# OP_Current_Fun-V0.net
KiCad netlist of a schematic drawn in EAGLE
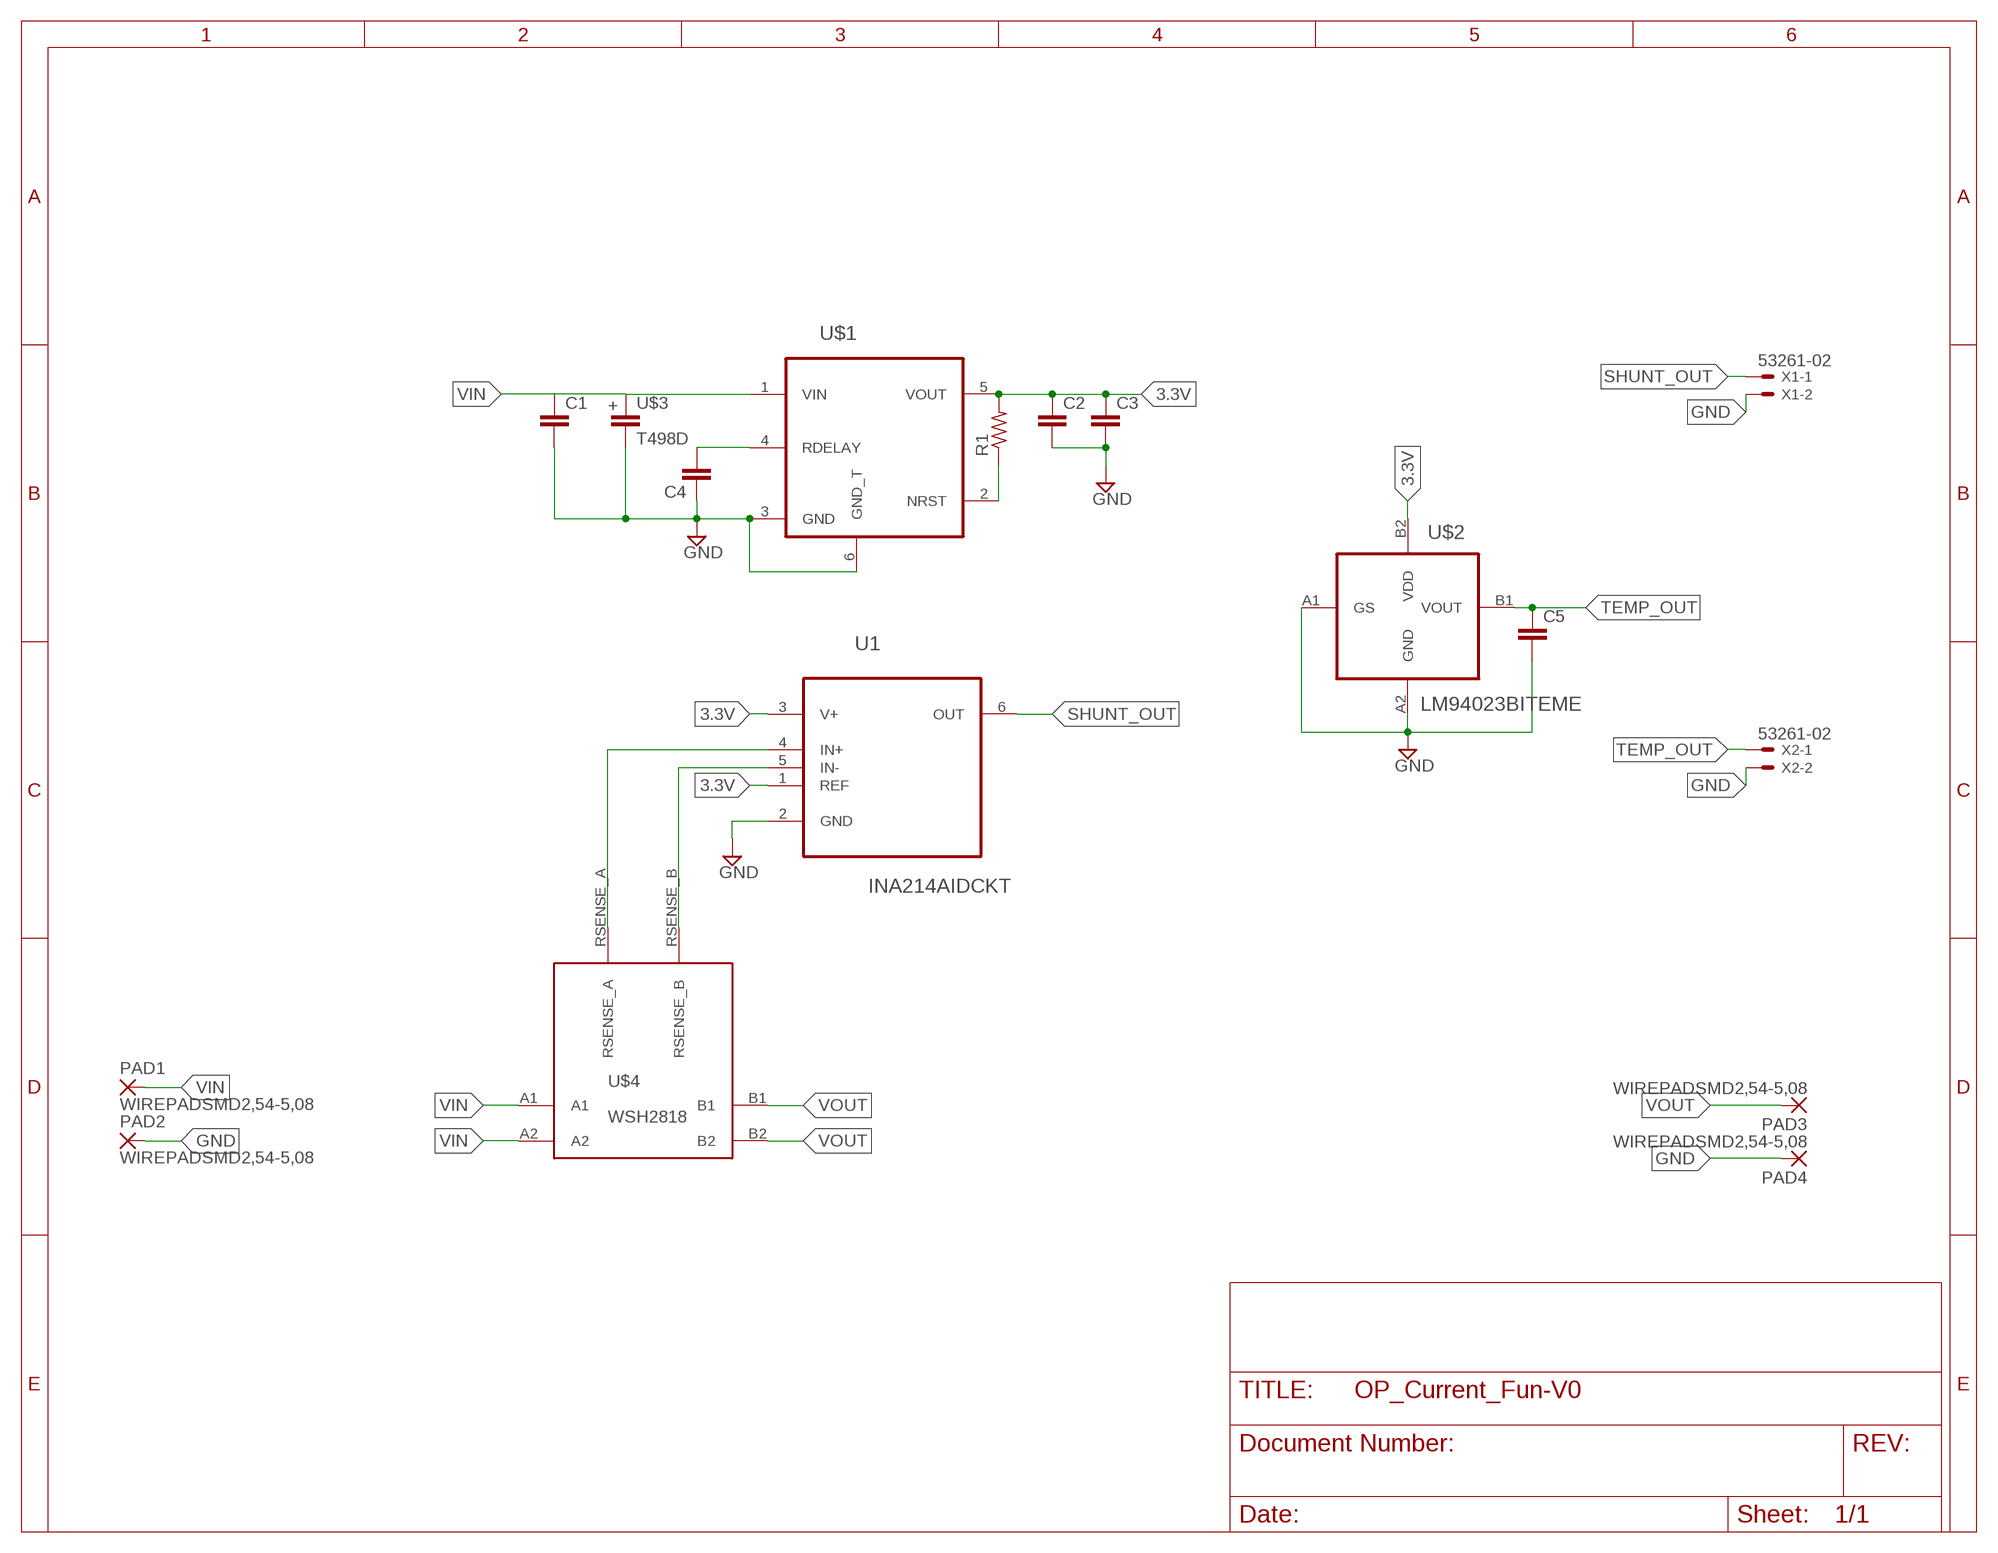
[diagram p0: schematic, sheet 1]

(export (version "E")
  (design (tool "Eeschema 10.0.6"))
  (components
    (comp (ref "C1")
      (value "C-EUC0603K")
      (footprint "eagle-import:C0603K")
      (libsource (lib "eagle-import") (part "C-EUC0603K"))
    )
    (comp (ref "C2")
      (value "C-EUC0603K")
      (footprint "eagle-import:C0603K")
      (libsource (lib "eagle-import") (part "C-EUC0603K"))
    )
    (comp (ref "C3")
      (value "C-EUC0603K")
      (footprint "eagle-import:C0603K")
      (libsource (lib "eagle-import") (part "C-EUC0603K"))
    )
    (comp (ref "C4")
      (value "C-EUC0805K")
      (footprint "eagle-import:C0805K")
      (libsource (lib "eagle-import") (part "C-EUC0805K"))
    )
    (comp (ref "C5")
      (value "C-EUC0603K")
      (footprint "eagle-import:C0603K")
      (libsource (lib "eagle-import") (part "C-EUC0603K"))
    )
    (comp (ref "PAD1")
      (value "WIREPADSMD2,54-5,08")
      (footprint "eagle-import:SMD2,54-5,08")
      (libsource (lib "eagle-import") (part "WIREPADSMD2,54-5,08"))
    )
    (comp (ref "PAD2")
      (value "WIREPADSMD2,54-5,08")
      (footprint "eagle-import:SMD2,54-5,08")
      (libsource (lib "eagle-import") (part "WIREPADSMD2,54-5,08"))
    )
    (comp (ref "PAD3")
      (value "WIREPADSMD2,54-5,08")
      (footprint "eagle-import:SMD2,54-5,08")
      (libsource (lib "eagle-import") (part "WIREPADSMD2,54-5,08"))
    )
    (comp (ref "PAD4")
      (value "WIREPADSMD2,54-5,08")
      (footprint "eagle-import:SMD2,54-5,08")
      (libsource (lib "eagle-import") (part "WIREPADSMD2,54-5,08"))
    )
    (comp (ref "R1")
      (value "R-US_R0402")
      (footprint "eagle-import:R0402")
      (libsource (lib "eagle-import") (part "R-US_R0402"))
    )
    (comp (ref "U$1")
      (value "TPS7A6033-Q1")
      (footprint "eagle-import:TO-263-5")
      (libsource (lib "eagle-import") (part "TPS7A6033-Q1"))
    )
    (comp (ref "U$2")
      (value "LM94023BITEME")
      (footprint "eagle-import:BGA4C40P2X2_76X76X63")
      (libsource (lib "eagle-import") (part "LM94023BITEME"))
    )
    (comp (ref "U$3")
      (value "T498D")
      (footprint "eagle-import:CT7343")
      (libsource (lib "eagle-import") (part "T498D"))
    )
    (comp (ref "U$4")
      (value "WSH2818")
      (footprint "eagle-import:2818")
      (libsource (lib "eagle-import") (part "WSH2818"))
    )
    (comp (ref "U1")
      (value "INA214AIDCKT")
      (footprint "eagle-import:SOT65P210X110-6N")
      (libsource (lib "eagle-import") (part "INA214AIDCKT"))
    )
    (comp (ref "X1")
      (value "53261-02")
      (footprint "eagle-import:53261-02")
      (libsource (lib "eagle-import") (part "53?-02261"))
    )
    (comp (ref "X2")
      (value "53261-02")
      (footprint "eagle-import:53261-02")
      (libsource (lib "eagle-import") (part "53?-02261"))
    )
  )
  (nets
    (net (code "1") (name "3.3V") (class "Default")
      (node (ref "C2") (pin "1") (pinfunction "1_1") (pintype "passive"))
      (node (ref "C3") (pin "1") (pinfunction "1_1") (pintype "passive"))
      (node (ref "R1") (pin "2") (pinfunction "2_2") (pintype "passive"))
      (node (ref "U$1") (pin "5") (pinfunction "VOUT_5") (pintype "output"))
      (node (ref "U$2") (pin "B2") (pinfunction "VDD_B2") (pintype "power_in"))
      (node (ref "U1") (pin "1") (pinfunction "REF_1") (pintype "input"))
      (node (ref "U1") (pin "3") (pinfunction "V+_3") (pintype "power_in"))
    )
    (net (code "2") (name "GND") (class "Default")
      (node (ref "C1") (pin "2") (pinfunction "2_2") (pintype "passive"))
      (node (ref "C2") (pin "2") (pinfunction "2_2") (pintype "passive"))
      (node (ref "C3") (pin "2") (pinfunction "2_2") (pintype "passive"))
      (node (ref "C4") (pin "1") (pinfunction "1_1") (pintype "passive"))
      (node (ref "C5") (pin "2") (pinfunction "2_2") (pintype "passive"))
      (node (ref "PAD2") (pin "1") (pinfunction "P_1") (pintype "passive"))
      (node (ref "PAD4") (pin "1") (pinfunction "P_1") (pintype "passive"))
      (node (ref "U$1") (pin "3") (pinfunction "GND_3") (pintype "passive"))
      (node (ref "U$1") (pin "6") (pinfunction "GND_T_6") (pintype "passive"))
      (node (ref "U$2") (pin "A1") (pinfunction "GS_A1") (pintype "input"))
      (node (ref "U$2") (pin "A2") (pinfunction "GND_A2") (pintype "passive"))
      (node (ref "U$3") (pin "-") (pinfunction "2_-") (pintype "passive"))
      (node (ref "U1") (pin "2") (pinfunction "GND_2") (pintype "passive"))
      (node (ref "X1") (pin "2") (pinfunction "S_2") (pintype "passive"))
      (node (ref "X2") (pin "2") (pinfunction "S_2") (pintype "passive"))
    )
    (net (code "3") (name "Net-(U$1-NRST)") (class "Default")
      (node (ref "R1") (pin "1") (pinfunction "1_1") (pintype "passive"))
      (node (ref "U$1") (pin "2") (pinfunction "NRST_2") (pintype "output"))
    )
    (net (code "4") (name "Net-(U$1-RDELAY)") (class "Default")
      (node (ref "C4") (pin "2") (pinfunction "2_2") (pintype "passive"))
      (node (ref "U$1") (pin "4") (pinfunction "RDELAY_4") (pintype "output"))
    )
    (net (code "5") (name "Net-(U1-IN+)") (class "Default")
      (node (ref "U$4") (pin "RSENSE_A") (pinfunction "RSENSE_A_RSENSE_A") (pintype "passive"))
      (node (ref "U1") (pin "4") (pinfunction "IN+_4") (pintype "input"))
    )
    (net (code "6") (name "Net-(U1-IN-)") (class "Default")
      (node (ref "U$4") (pin "RSENSE_B") (pinfunction "RSENSE_B_RSENSE_B") (pintype "passive"))
      (node (ref "U1") (pin "5") (pinfunction "IN-_5") (pintype "input"))
    )
    (net (code "7") (name "SHUNT_OUT") (class "Default")
      (node (ref "U1") (pin "6") (pinfunction "OUT_6") (pintype "output"))
      (node (ref "X1") (pin "1") (pinfunction "S_1") (pintype "passive"))
    )
    (net (code "8") (name "TEMP_OUT") (class "Default")
      (node (ref "C5") (pin "1") (pinfunction "1_1") (pintype "passive"))
      (node (ref "U$2") (pin "B1") (pinfunction "VOUT_B1") (pintype "output"))
      (node (ref "X2") (pin "1") (pinfunction "S_1") (pintype "passive"))
    )
    (net (code "9") (name "VIN") (class "Default")
      (node (ref "C1") (pin "1") (pinfunction "1_1") (pintype "passive"))
      (node (ref "PAD1") (pin "1") (pinfunction "P_1") (pintype "passive"))
      (node (ref "U$1") (pin "1") (pinfunction "VIN_1") (pintype "power_in"))
      (node (ref "U$3") (pin "+") (pinfunction "1_+") (pintype "passive"))
      (node (ref "U$4") (pin "A1") (pinfunction "A1_A1") (pintype "passive"))
      (node (ref "U$4") (pin "A2") (pinfunction "A2_A2") (pintype "passive"))
    )
    (net (code "10") (name "VOUT") (class "Default")
      (node (ref "PAD3") (pin "1") (pinfunction "P_1") (pintype "passive"))
      (node (ref "U$4") (pin "B1") (pinfunction "B1_B1") (pintype "passive"))
      (node (ref "U$4") (pin "B2") (pinfunction "B2_B2") (pintype "passive"))
    )
  )
)
